# LEDBoard.net
KiCad netlist of a schematic drawn in EAGLE
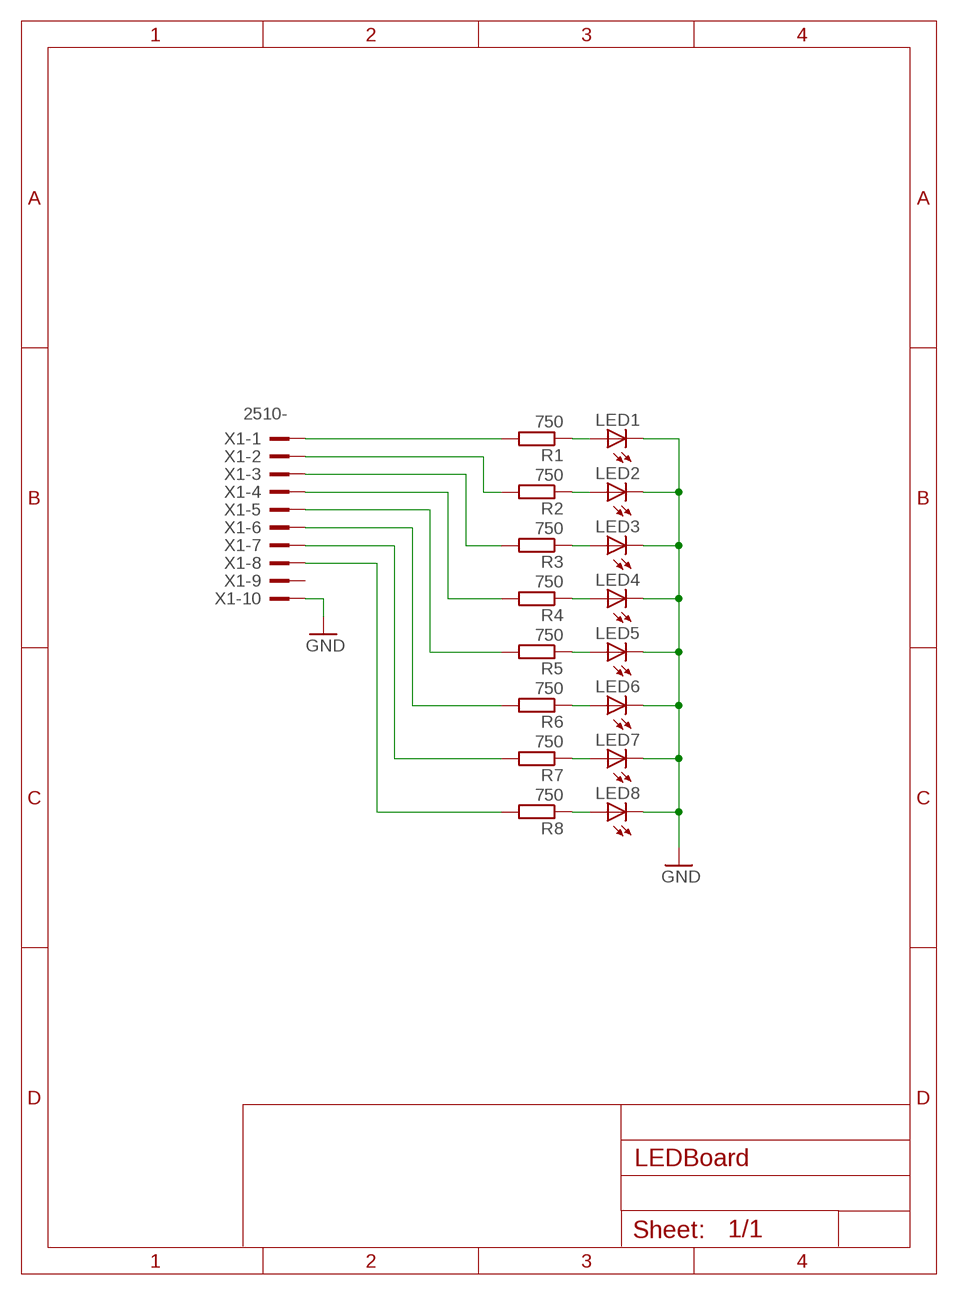
[diagram p0: schematic, sheet 1]

(export (version "E")
  (design (tool "Eeschema 10.0.6"))
  (components
    (comp (ref "LED1")
      (value "LED3MM")
      (footprint "eagle-import:LED3MM")
      (libsource (lib "eagle-import") (part "LED3MM"))
    )
    (comp (ref "LED2")
      (value "LED3MM")
      (footprint "eagle-import:LED3MM")
      (libsource (lib "eagle-import") (part "LED3MM"))
    )
    (comp (ref "LED3")
      (value "LED3MM")
      (footprint "eagle-import:LED3MM")
      (libsource (lib "eagle-import") (part "LED3MM"))
    )
    (comp (ref "LED4")
      (value "LED3MM")
      (footprint "eagle-import:LED3MM")
      (libsource (lib "eagle-import") (part "LED3MM"))
    )
    (comp (ref "LED5")
      (value "LED3MM")
      (footprint "eagle-import:LED3MM")
      (libsource (lib "eagle-import") (part "LED3MM"))
    )
    (comp (ref "LED6")
      (value "LED3MM")
      (footprint "eagle-import:LED3MM")
      (libsource (lib "eagle-import") (part "LED3MM"))
    )
    (comp (ref "LED7")
      (value "LED3MM")
      (footprint "eagle-import:LED3MM")
      (libsource (lib "eagle-import") (part "LED3MM"))
    )
    (comp (ref "LED8")
      (value "LED3MM")
      (footprint "eagle-import:LED3MM")
      (libsource (lib "eagle-import") (part "LED3MM"))
    )
    (comp (ref "R1")
      (value "750")
      (footprint "eagle-import:R1206")
      (libsource (lib "eagle-import") (part "R-EU_R1206"))
    )
    (comp (ref "R2")
      (value "750")
      (footprint "eagle-import:R1206")
      (libsource (lib "eagle-import") (part "R-EU_R1206"))
    )
    (comp (ref "R3")
      (value "750")
      (footprint "eagle-import:R1206")
      (libsource (lib "eagle-import") (part "R-EU_R1206"))
    )
    (comp (ref "R4")
      (value "750")
      (footprint "eagle-import:R1206")
      (libsource (lib "eagle-import") (part "R-EU_R1206"))
    )
    (comp (ref "R5")
      (value "750")
      (footprint "eagle-import:R1206")
      (libsource (lib "eagle-import") (part "R-EU_R1206"))
    )
    (comp (ref "R6")
      (value "750")
      (footprint "eagle-import:R1206")
      (libsource (lib "eagle-import") (part "R-EU_R1206"))
    )
    (comp (ref "R7")
      (value "750")
      (footprint "eagle-import:R1206")
      (libsource (lib "eagle-import") (part "R-EU_R1206"))
    )
    (comp (ref "R8")
      (value "750")
      (footprint "eagle-import:R1206")
      (libsource (lib "eagle-import") (part "R-EU_R1206"))
    )
    (comp (ref "X1")
      (value "2510-")
      (footprint "eagle-import:PAK100_2500-10")
      (fields (field (name "MF") "3M") (field (name "MPN") "2510-6002UB"))
      (libsource (lib "eagle-import") (part "2510-"))
    )
  )
  (nets
    (net (code "1") (name "GND") (class "Default")
      (node (ref "LED1") (pin "K") (pinfunction "C_K") (pintype "passive"))
      (node (ref "LED2") (pin "K") (pinfunction "C_K") (pintype "passive"))
      (node (ref "LED3") (pin "K") (pinfunction "C_K") (pintype "passive"))
      (node (ref "LED4") (pin "K") (pinfunction "C_K") (pintype "passive"))
      (node (ref "LED5") (pin "K") (pinfunction "C_K") (pintype "passive"))
      (node (ref "LED6") (pin "K") (pinfunction "C_K") (pintype "passive"))
      (node (ref "LED7") (pin "K") (pinfunction "C_K") (pintype "passive"))
      (node (ref "LED8") (pin "K") (pinfunction "C_K") (pintype "passive"))
      (node (ref "X1") (pin "10") (pinfunction "KL_10") (pintype "passive"))
    )
    (net (code "2") (name "Net-(LED1-PadA)") (class "Default")
      (node (ref "LED1") (pin "A") (pinfunction "A_A") (pintype "passive"))
      (node (ref "R1") (pin "1") (pinfunction "1_1") (pintype "passive"))
    )
    (net (code "3") (name "Net-(LED2-PadA)") (class "Default")
      (node (ref "LED2") (pin "A") (pinfunction "A_A") (pintype "passive"))
      (node (ref "R2") (pin "1") (pinfunction "1_1") (pintype "passive"))
    )
    (net (code "4") (name "Net-(LED3-PadA)") (class "Default")
      (node (ref "LED3") (pin "A") (pinfunction "A_A") (pintype "passive"))
      (node (ref "R3") (pin "1") (pinfunction "1_1") (pintype "passive"))
    )
    (net (code "5") (name "Net-(LED4-PadA)") (class "Default")
      (node (ref "LED4") (pin "A") (pinfunction "A_A") (pintype "passive"))
      (node (ref "R4") (pin "1") (pinfunction "1_1") (pintype "passive"))
    )
    (net (code "6") (name "Net-(LED5-PadA)") (class "Default")
      (node (ref "LED5") (pin "A") (pinfunction "A_A") (pintype "passive"))
      (node (ref "R5") (pin "1") (pinfunction "1_1") (pintype "passive"))
    )
    (net (code "7") (name "Net-(LED6-PadA)") (class "Default")
      (node (ref "LED6") (pin "A") (pinfunction "A_A") (pintype "passive"))
      (node (ref "R6") (pin "1") (pinfunction "1_1") (pintype "passive"))
    )
    (net (code "8") (name "Net-(LED7-PadA)") (class "Default")
      (node (ref "LED7") (pin "A") (pinfunction "A_A") (pintype "passive"))
      (node (ref "R7") (pin "1") (pinfunction "1_1") (pintype "passive"))
    )
    (net (code "9") (name "Net-(LED8-PadA)") (class "Default")
      (node (ref "LED8") (pin "A") (pinfunction "A_A") (pintype "passive"))
      (node (ref "R8") (pin "1") (pinfunction "1_1") (pintype "passive"))
    )
    (net (code "10") (name "Net-(X1A-KL)") (class "Default")
      (node (ref "R1") (pin "2") (pinfunction "2_2") (pintype "passive"))
      (node (ref "X1") (pin "1") (pinfunction "KL_1") (pintype "passive"))
    )
    (net (code "11") (name "Net-(X1C-KL)") (class "Default")
      (node (ref "R2") (pin "2") (pinfunction "2_2") (pintype "passive"))
      (node (ref "X1") (pin "2") (pinfunction "KL_2") (pintype "passive"))
    )
    (net (code "12") (name "Net-(X1D-KL)") (class "Default")
      (node (ref "R3") (pin "2") (pinfunction "2_2") (pintype "passive"))
      (node (ref "X1") (pin "3") (pinfunction "KL_3") (pintype "passive"))
    )
    (net (code "13") (name "Net-(X1E-KL)") (class "Default")
      (node (ref "R4") (pin "2") (pinfunction "2_2") (pintype "passive"))
      (node (ref "X1") (pin "4") (pinfunction "KL_4") (pintype "passive"))
    )
    (net (code "14") (name "Net-(X1F-KL)") (class "Default")
      (node (ref "R5") (pin "2") (pinfunction "2_2") (pintype "passive"))
      (node (ref "X1") (pin "5") (pinfunction "KL_5") (pintype "passive"))
    )
    (net (code "15") (name "Net-(X1G-KL)") (class "Default")
      (node (ref "R6") (pin "2") (pinfunction "2_2") (pintype "passive"))
      (node (ref "X1") (pin "6") (pinfunction "KL_6") (pintype "passive"))
    )
    (net (code "16") (name "Net-(X1H-KL)") (class "Default")
      (node (ref "R7") (pin "2") (pinfunction "2_2") (pintype "passive"))
      (node (ref "X1") (pin "7") (pinfunction "KL_7") (pintype "passive"))
    )
    (net (code "17") (name "Net-(X1I-KL)") (class "Default")
      (node (ref "R8") (pin "2") (pinfunction "2_2") (pintype "passive"))
      (node (ref "X1") (pin "8") (pinfunction "KL_8") (pintype "passive"))
    )
    (net (code "18") (name "unconnected-(X1J-KL-Pad9)") (class "Default")
      (node (ref "X1") (pin "9") (pinfunction "KL_9") (pintype "passive"))
    )
  )
)
